# main_board.net
KiCad netlist of a schematic drawn in EAGLE
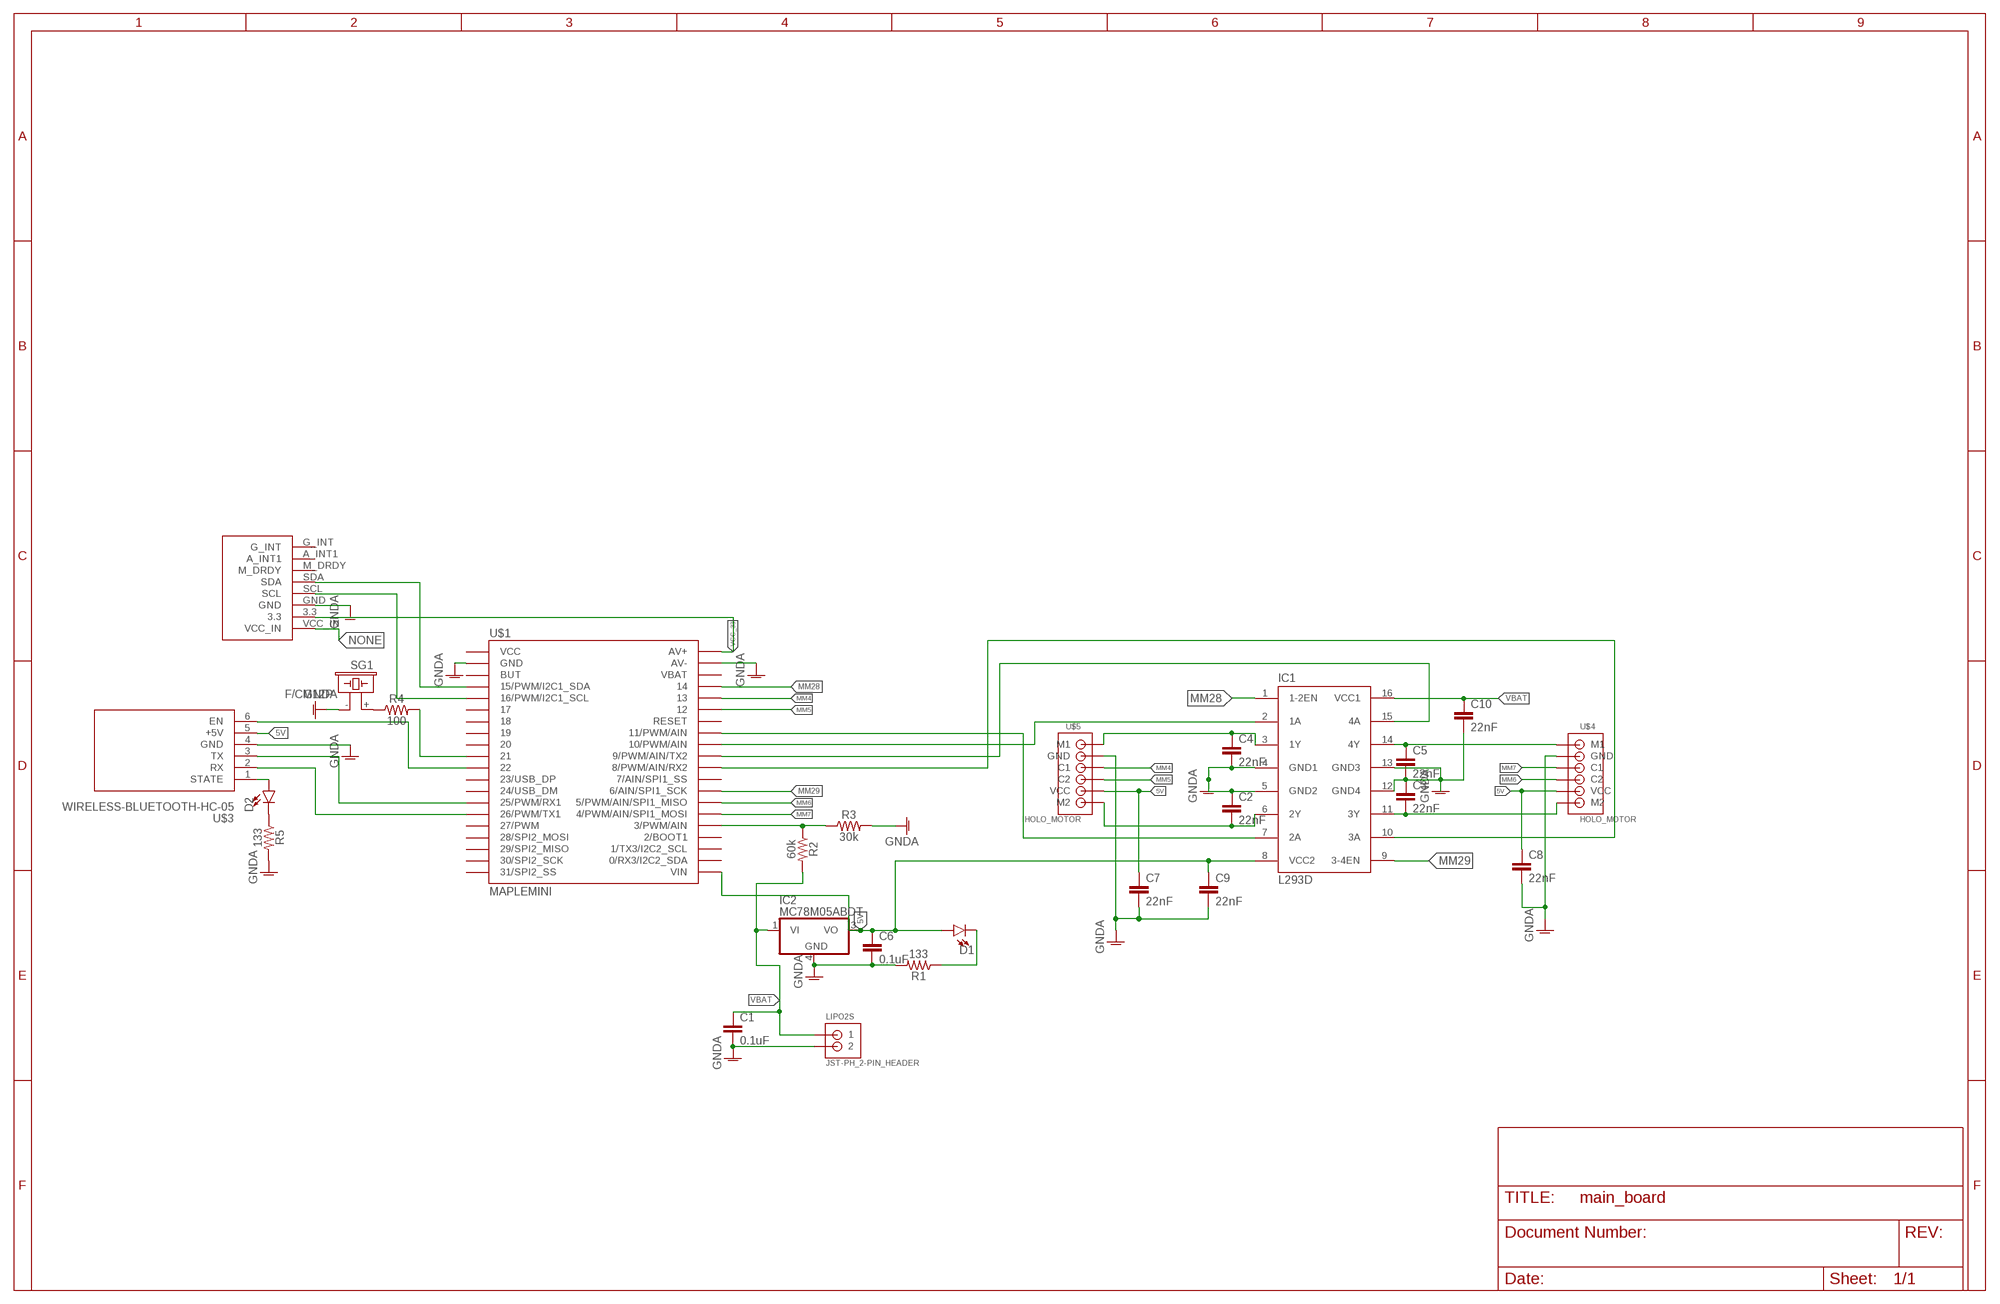
[diagram p0: schematic, sheet 1]

(export (version "E")
  (design (tool "Eeschema 10.0.6"))
  (components
    (comp (ref "C1")
      (value "0.1uF")
      (footprint "eagle-import:0603")
      (libsource (lib "eagle-import") (part "0.1UF-0603-25V-(+80/-20%)"))
    )
    (comp (ref "C2")
      (value "22nF")
      (footprint "eagle-import:0603")
      (libsource (lib "eagle-import") (part "22NF/22,000PF-0603-50V-10%"))
    )
    (comp (ref "C3")
      (value "22nF")
      (footprint "eagle-import:0603")
      (libsource (lib "eagle-import") (part "22NF/22,000PF-0603-50V-10%"))
    )
    (comp (ref "C4")
      (value "22nF")
      (footprint "eagle-import:0603")
      (libsource (lib "eagle-import") (part "22NF/22,000PF-0603-50V-10%"))
    )
    (comp (ref "C5")
      (value "22nF")
      (footprint "eagle-import:0603")
      (libsource (lib "eagle-import") (part "22NF/22,000PF-0603-50V-10%"))
    )
    (comp (ref "C6")
      (value "0.1uF")
      (footprint "eagle-import:0603")
      (libsource (lib "eagle-import") (part "0.1UF-0603-25V-(+80/-20%)"))
    )
    (comp (ref "C7")
      (value "22nF")
      (footprint "eagle-import:0603")
      (fields (field (name "PROD_ID") "CAP-07885"))
      (libsource (lib "eagle-import") (part "22NF/22,000PF-0603-50V-10%"))
    )
    (comp (ref "C8")
      (value "22nF")
      (footprint "eagle-import:0603")
      (fields (field (name "PROD_ID") "CAP-07885"))
      (libsource (lib "eagle-import") (part "22NF/22,000PF-0603-50V-10%"))
    )
    (comp (ref "C9")
      (value "22nF")
      (footprint "eagle-import:0603")
      (fields (field (name "PROD_ID") "CAP-07885"))
      (libsource (lib "eagle-import") (part "22NF/22,000PF-0603-50V-10%"))
    )
    (comp (ref "C10")
      (value "22nF")
      (footprint "eagle-import:0603")
      (fields (field (name "PROD_ID") "CAP-07885"))
      (libsource (lib "eagle-import") (part "22NF/22,000PF-0603-50V-10%"))
    )
    (comp (ref "D1")
      (value "LED-FKIT-1206")
      (footprint "eagle-import:FKIT-LED-1206")
      (libsource (lib "eagle-import") (part "LED-FKIT-1206"))
    )
    (comp (ref "D2")
      (value "LED-FKIT-1206")
      (footprint "eagle-import:FKIT-LED-1206")
      (libsource (lib "eagle-import") (part "LED-FKIT-1206"))
    )
    (comp (ref "IC1")
      (value "L293D")
      (footprint "eagle-import:DIL16")
      (libsource (lib "eagle-import") (part "L293D"))
    )
    (comp (ref "IC2")
      (value "MC78M05ABDT")
      (footprint "eagle-import:DPACK_3")
      (libsource (lib "eagle-import") (part "MC78M05ABDT"))
    )
    (comp (ref "LIPO2S")
      (value "JST-PH_2-PIN_HEADER")
      (footprint "eagle-import:JST_B2B-PH_HEADER")
      (libsource (lib "eagle-import") (part "JST-PH_2-PIN_HEADER"))
    )
    (comp (ref "R1")
      (value "133")
      (footprint "eagle-import:0603")
      (libsource (lib "eagle-import") (part "0.27OHM-0603-1/10W-1%"))
    )
    (comp (ref "R2")
      (value "60k")
      (footprint "eagle-import:0603")
      (libsource (lib "eagle-import") (part "0.27OHM-0603-1/10W-1%"))
    )
    (comp (ref "R3")
      (value "30k")
      (footprint "eagle-import:0603")
      (libsource (lib "eagle-import") (part "0.27OHM-0603-1/10W-1%"))
    )
    (comp (ref "R4")
      (value "100")
      (footprint "eagle-import:0603")
      (libsource (lib "eagle-import") (part "0.27OHM-0603-1/10W-1%"))
    )
    (comp (ref "R5")
      (value "133")
      (footprint "eagle-import:0603")
      (libsource (lib "eagle-import") (part "0.27OHM-0603-1/10W-1%"))
    )
    (comp (ref "SG1")
      (value "F/CM12P")
      (footprint "eagle-import:F_CM12P")
      (libsource (lib "eagle-import") (part "F/CM12P"))
    )
    (comp (ref "U$1")
      (value "MAPLEMINI")
      (footprint "eagle-import:20-DIP")
      (libsource (lib "eagle-import") (part "MAPLEMINI"))
    )
    (comp (ref "U$3")
      (value "WIRELESS-BLUETOOTH-HC-05")
      (footprint "eagle-import:WIRELESS-BLUETOOTH-HC-05")
      (libsource (lib "eagle-import") (part "WIRELESS-BLUETOOTH-HC-05"))
    )
    (comp (ref "U$4")
      (value "HOLO_MOTOR")
      (footprint "eagle-import:HOLO_MOTOR")
      (libsource (lib "eagle-import") (part "HOLO_MOTOR"))
    )
    (comp (ref "U$5")
      (value "HOLO_MOTOR")
      (footprint "eagle-import:HOLO_MOTOR")
      (libsource (lib "eagle-import") (part "HOLO_MOTOR"))
    )
    (comp (ref "U$6")
      (value "GY-85")
      (footprint "eagle-import:GY-85")
      (libsource (lib "eagle-import") (part "GY-85"))
    )
  )
  (nets
    (net (code "1") (name "5V") (class "Default")
      (node (ref "C6") (pin "1") (pinfunction "1_1") (pintype "passive"))
      (node (ref "C7") (pin "1") (pinfunction "1_1") (pintype "passive"))
      (node (ref "C8") (pin "1") (pinfunction "1_1") (pintype "passive"))
      (node (ref "C9") (pin "1") (pinfunction "1_1") (pintype "passive"))
      (node (ref "D1") (pin "A") (pinfunction "A_A") (pintype "passive"))
      (node (ref "IC1") (pin "8") (pinfunction "VCC2_8") (pintype "power_in"))
      (node (ref "IC2") (pin "3") (pinfunction "VO_3") (pintype "passive"))
      (node (ref "U$1") (pin "21") (pinfunction "VIN_21") (pintype "bidirectional"))
      (node (ref "U$3") (pin "5") (pinfunction "+5V_5") (pintype "power_in"))
      (node (ref "U$4") (pin "5") (pinfunction "VCC_5") (pintype "bidirectional"))
      (node (ref "U$5") (pin "5") (pinfunction "VCC_5") (pintype "bidirectional"))
    )
    (net (code "2") (name "GNDA") (class "Default")
      (node (ref "C1") (pin "2") (pinfunction "2_2") (pintype "passive"))
      (node (ref "C10") (pin "2") (pinfunction "2_2") (pintype "passive"))
      (node (ref "C2") (pin "1") (pinfunction "1_1") (pintype "passive"))
      (node (ref "C3") (pin "1") (pinfunction "1_1") (pintype "passive"))
      (node (ref "C4") (pin "2") (pinfunction "2_2") (pintype "passive"))
      (node (ref "C5") (pin "2") (pinfunction "2_2") (pintype "passive"))
      (node (ref "C6") (pin "2") (pinfunction "2_2") (pintype "passive"))
      (node (ref "C7") (pin "2") (pinfunction "2_2") (pintype "passive"))
      (node (ref "C8") (pin "2") (pinfunction "2_2") (pintype "passive"))
      (node (ref "C9") (pin "2") (pinfunction "2_2") (pintype "passive"))
      (node (ref "IC1") (pin "12") (pinfunction "GND4_12") (pintype "power_in"))
      (node (ref "IC1") (pin "13") (pinfunction "GND3_13") (pintype "power_in"))
      (node (ref "IC1") (pin "4") (pinfunction "GND1_4") (pintype "power_in"))
      (node (ref "IC1") (pin "5") (pinfunction "GND2_5") (pintype "power_in"))
      (node (ref "IC2") (pin "4") (pinfunction "GND_4") (pintype "passive"))
      (node (ref "LIPO2S") (pin "P2") (pinfunction "2_P2") (pintype "bidirectional"))
      (node (ref "R1") (pin "2") (pinfunction "2_2") (pintype "passive"))
      (node (ref "R3") (pin "2") (pinfunction "2_2") (pintype "passive"))
      (node (ref "R5") (pin "2") (pinfunction "2_2") (pintype "passive"))
      (node (ref "SG1") (pin "-") (pinfunction "2_-") (pintype "passive"))
      (node (ref "U$1") (pin "2") (pinfunction "GND_2") (pintype "bidirectional"))
      (node (ref "U$1") (pin "39") (pinfunction "AV-_39") (pintype "bidirectional"))
      (node (ref "U$3") (pin "4") (pinfunction "GND_4") (pintype "power_in"))
      (node (ref "U$4") (pin "2") (pinfunction "GND_2") (pintype "bidirectional"))
      (node (ref "U$5") (pin "2") (pinfunction "GND_2") (pintype "bidirectional"))
      (node (ref "U$6") (pin "GND") (pinfunction "GND_GND") (pintype "bidirectional"))
    )
    (net (code "3") (name "MM4") (class "Default")
      (node (ref "U$1") (pin "36") (pinfunction "13_36") (pintype "bidirectional"))
      (node (ref "U$5") (pin "3") (pinfunction "C1_3") (pintype "bidirectional"))
    )
    (net (code "4") (name "MM5") (class "Default")
      (node (ref "U$1") (pin "35") (pinfunction "12_35") (pintype "bidirectional"))
      (node (ref "U$5") (pin "4") (pinfunction "C2_4") (pintype "bidirectional"))
    )
    (net (code "5") (name "MM6") (class "Default")
      (node (ref "U$1") (pin "27") (pinfunction "5/PWM/AIN/SPI1_MISO_27") (pintype "bidirectional"))
      (node (ref "U$4") (pin "4") (pinfunction "C2_4") (pintype "bidirectional"))
    )
    (net (code "6") (name "MM7") (class "Default")
      (node (ref "U$1") (pin "26") (pinfunction "4/PWM/AIN/SPI1_MOSI_26") (pintype "bidirectional"))
      (node (ref "U$4") (pin "3") (pinfunction "C1_3") (pintype "bidirectional"))
    )
    (net (code "7") (name "MM28") (class "Default")
      (node (ref "IC1") (pin "1") (pinfunction "1-2EN_1") (pintype "input"))
      (node (ref "U$1") (pin "37") (pinfunction "14_37") (pintype "bidirectional"))
    )
    (net (code "8") (name "MM29") (class "Default")
      (node (ref "IC1") (pin "9") (pinfunction "3-4EN_9") (pintype "input"))
      (node (ref "U$1") (pin "28") (pinfunction "6/AIN/SPI1_SCK_28") (pintype "bidirectional"))
    )
    (net (code "9") (name "NONE") (class "Default")
      (node (ref "U$6") (pin "VCC_IN") (pinfunction "VCC_IN_VCC_IN") (pintype "bidirectional"))
    )
    (net (code "10") (name "Net-(D1-PadC)") (class "Default")
      (node (ref "D1") (pin "C") (pinfunction "C_C") (pintype "passive"))
      (node (ref "R1") (pin "1") (pinfunction "1_1") (pintype "passive"))
    )
    (net (code "11") (name "Net-(D2-PadC)") (class "Default")
      (node (ref "D2") (pin "C") (pinfunction "C_C") (pintype "passive"))
      (node (ref "R5") (pin "1") (pinfunction "1_1") (pintype "passive"))
    )
    (net (code "12") (name "Net-(IC1-1A)") (class "Default")
      (node (ref "IC1") (pin "2") (pinfunction "1A_2") (pintype "input"))
      (node (ref "U$1") (pin "32") (pinfunction "10/PWM/AIN_32") (pintype "bidirectional"))
    )
    (net (code "13") (name "Net-(IC1-1Y)") (class "Default")
      (node (ref "C4") (pin "1") (pinfunction "1_1") (pintype "passive"))
      (node (ref "IC1") (pin "3") (pinfunction "1Y_3") (pintype "output"))
      (node (ref "U$5") (pin "1") (pinfunction "M1_1") (pintype "bidirectional"))
    )
    (net (code "14") (name "Net-(IC1-2A)") (class "Default")
      (node (ref "IC1") (pin "7") (pinfunction "2A_7") (pintype "input"))
      (node (ref "U$1") (pin "33") (pinfunction "11/PWM/AIN_33") (pintype "bidirectional"))
    )
    (net (code "15") (name "Net-(IC1-2Y)") (class "Default")
      (node (ref "C2") (pin "2") (pinfunction "2_2") (pintype "passive"))
      (node (ref "IC1") (pin "6") (pinfunction "2Y_6") (pintype "output"))
      (node (ref "U$5") (pin "6") (pinfunction "M2_6") (pintype "bidirectional"))
    )
    (net (code "16") (name "Net-(IC1-3A)") (class "Default")
      (node (ref "IC1") (pin "10") (pinfunction "3A_10") (pintype "input"))
      (node (ref "U$1") (pin "30") (pinfunction "8/PWM/AIN/RX2_30") (pintype "bidirectional"))
    )
    (net (code "17") (name "Net-(IC1-3Y)") (class "Default")
      (node (ref "C3") (pin "2") (pinfunction "2_2") (pintype "passive"))
      (node (ref "IC1") (pin "11") (pinfunction "3Y_11") (pintype "output"))
      (node (ref "U$4") (pin "6") (pinfunction "M2_6") (pintype "bidirectional"))
    )
    (net (code "18") (name "Net-(IC1-4A)") (class "Default")
      (node (ref "IC1") (pin "15") (pinfunction "4A_15") (pintype "input"))
      (node (ref "U$1") (pin "31") (pinfunction "9/PWM/AIN/TX2_31") (pintype "bidirectional"))
    )
    (net (code "19") (name "Net-(IC1-4Y)") (class "Default")
      (node (ref "C5") (pin "1") (pinfunction "1_1") (pintype "passive"))
      (node (ref "IC1") (pin "14") (pinfunction "4Y_14") (pintype "output"))
      (node (ref "U$4") (pin "1") (pinfunction "M1_1") (pintype "bidirectional"))
    )
    (net (code "20") (name "Net-(SG1-1)") (class "Default")
      (node (ref "R4") (pin "1") (pinfunction "1_1") (pintype "passive"))
      (node (ref "SG1") (pin "+") (pinfunction "1_+") (pintype "passive"))
    )
    (net (code "21") (name "Net-(U$1-3{slash}PWM{slash}AIN)") (class "Default")
      (node (ref "R2") (pin "1") (pinfunction "1_1") (pintype "passive"))
      (node (ref "R3") (pin "1") (pinfunction "1_1") (pintype "passive"))
      (node (ref "U$1") (pin "25") (pinfunction "3/PWM/AIN_25") (pintype "bidirectional"))
    )
    (net (code "22") (name "Net-(U$1-15{slash}PWM{slash}I2C1_SDA)") (class "Default")
      (node (ref "U$1") (pin "4") (pinfunction "15/PWM/I2C1_SDA_4") (pintype "bidirectional"))
      (node (ref "U$6") (pin "SDA") (pinfunction "SDA_SDA") (pintype "bidirectional"))
    )
    (net (code "23") (name "Net-(U$1-16{slash}PWM{slash}I2C1_SCL)") (class "Default")
      (node (ref "U$1") (pin "5") (pinfunction "16/PWM/I2C1_SCL_5") (pintype "bidirectional"))
      (node (ref "U$6") (pin "SCL") (pinfunction "SCL_SCL") (pintype "bidirectional"))
    )
    (net (code "24") (name "Net-(U$1-21)") (class "Default")
      (node (ref "R4") (pin "2") (pinfunction "2_2") (pintype "passive"))
      (node (ref "U$1") (pin "10") (pinfunction "21_10") (pintype "bidirectional"))
    )
    (net (code "25") (name "Net-(U$1-22)") (class "Default")
      (node (ref "U$1") (pin "11") (pinfunction "22_11") (pintype "bidirectional"))
      (node (ref "U$3") (pin "6") (pinfunction "EN_6") (pintype "bidirectional"))
    )
    (net (code "26") (name "Net-(U$1-25{slash}PWM{slash}RX1)") (class "Default")
      (node (ref "U$1") (pin "14") (pinfunction "25/PWM/RX1_14") (pintype "bidirectional"))
      (node (ref "U$3") (pin "3") (pinfunction "TX_3") (pintype "bidirectional"))
    )
    (net (code "27") (name "Net-(U$1-26{slash}PWM{slash}TX1)") (class "Default")
      (node (ref "U$1") (pin "15") (pinfunction "26/PWM/TX1_15") (pintype "bidirectional"))
      (node (ref "U$3") (pin "2") (pinfunction "RX_2") (pintype "bidirectional"))
    )
    (net (code "28") (name "Net-(U$3-STATE)") (class "Default")
      (node (ref "D2") (pin "A") (pinfunction "A_A") (pintype "passive"))
      (node (ref "U$3") (pin "1") (pinfunction "STATE_1") (pintype "bidirectional"))
    )
    (net (code "29") (name "VBAT") (class "Default")
      (node (ref "C1") (pin "1") (pinfunction "1_1") (pintype "passive"))
      (node (ref "C10") (pin "1") (pinfunction "1_1") (pintype "passive"))
      (node (ref "IC1") (pin "16") (pinfunction "VCC1_16") (pintype "power_in"))
      (node (ref "IC2") (pin "1") (pinfunction "VI_1") (pintype "input"))
      (node (ref "LIPO2S") (pin "P1") (pinfunction "1_P1") (pintype "bidirectional"))
      (node (ref "R2") (pin "2") (pinfunction "2_2") (pintype "passive"))
    )
    (net (code "30") (name "VCC_33") (class "Default")
      (node (ref "U$1") (pin "40") (pinfunction "AV+_40") (pintype "bidirectional"))
      (node (ref "U$6") (pin "3.3") (pinfunction "3.3_3.3") (pintype "bidirectional"))
    )
    (net (code "31") (name "unconnected-(U$1-0{slash}RX3{slash}I2C2_SDA-Pad22)") (class "Default")
      (node (ref "U$1") (pin "22") (pinfunction "0/RX3/I2C2_SDA_22") (pintype "bidirectional"))
    )
    (net (code "32") (name "unconnected-(U$1-1{slash}TX3{slash}I2C2_SCL-Pad23)") (class "Default")
      (node (ref "U$1") (pin "23") (pinfunction "1/TX3/I2C2_SCL_23") (pintype "bidirectional"))
    )
    (net (code "33") (name "unconnected-(U$1-2{slash}BOOT1-Pad24)") (class "Default")
      (node (ref "U$1") (pin "24") (pinfunction "2/BOOT1_24") (pintype "bidirectional"))
    )
    (net (code "34") (name "unconnected-(U$1-7{slash}AIN{slash}SPI1_SS-Pad29)") (class "Default")
      (node (ref "U$1") (pin "29") (pinfunction "7/AIN/SPI1_SS_29") (pintype "bidirectional"))
    )
    (net (code "35") (name "unconnected-(U$1-17-Pad6)") (class "Default")
      (node (ref "U$1") (pin "6") (pinfunction "17_6") (pintype "bidirectional"))
    )
    (net (code "36") (name "unconnected-(U$1-18-Pad7)") (class "Default")
      (node (ref "U$1") (pin "7") (pinfunction "18_7") (pintype "bidirectional"))
    )
    (net (code "37") (name "unconnected-(U$1-19-Pad8)") (class "Default")
      (node (ref "U$1") (pin "8") (pinfunction "19_8") (pintype "bidirectional"))
    )
    (net (code "38") (name "unconnected-(U$1-20-Pad9)") (class "Default")
      (node (ref "U$1") (pin "9") (pinfunction "20_9") (pintype "bidirectional"))
    )
    (net (code "39") (name "unconnected-(U$1-23{slash}USB_DP-Pad12)") (class "Default")
      (node (ref "U$1") (pin "12") (pinfunction "23/USB_DP_12") (pintype "bidirectional"))
    )
    (net (code "40") (name "unconnected-(U$1-24{slash}USB_DM-Pad13)") (class "Default")
      (node (ref "U$1") (pin "13") (pinfunction "24/USB_DM_13") (pintype "bidirectional"))
    )
    (net (code "41") (name "unconnected-(U$1-27{slash}PWM-Pad16)") (class "Default")
      (node (ref "U$1") (pin "16") (pinfunction "27/PWM_16") (pintype "bidirectional"))
    )
    (net (code "42") (name "unconnected-(U$1-28{slash}SPI2_MOSI-Pad17)") (class "Default")
      (node (ref "U$1") (pin "17") (pinfunction "28/SPI2_MOSI_17") (pintype "bidirectional"))
    )
    (net (code "43") (name "unconnected-(U$1-29{slash}SPI2_MISO-Pad18)") (class "Default")
      (node (ref "U$1") (pin "18") (pinfunction "29/SPI2_MISO_18") (pintype "bidirectional"))
    )
    (net (code "44") (name "unconnected-(U$1-30{slash}SPI2_SCK-Pad19)") (class "Default")
      (node (ref "U$1") (pin "19") (pinfunction "30/SPI2_SCK_19") (pintype "bidirectional"))
    )
    (net (code "45") (name "unconnected-(U$1-31{slash}SPI2_SS-Pad20)") (class "Default")
      (node (ref "U$1") (pin "20") (pinfunction "31/SPI2_SS_20") (pintype "bidirectional"))
    )
    (net (code "46") (name "unconnected-(U$1-BUT-Pad3)") (class "Default")
      (node (ref "U$1") (pin "3") (pinfunction "BUT_3") (pintype "bidirectional"))
    )
    (net (code "47") (name "unconnected-(U$1-RESET-Pad34)") (class "Default")
      (node (ref "U$1") (pin "34") (pinfunction "RESET_34") (pintype "bidirectional"))
    )
    (net (code "48") (name "unconnected-(U$1-VBAT-Pad38)") (class "Default")
      (node (ref "U$1") (pin "38") (pinfunction "VBAT_38") (pintype "bidirectional"))
    )
    (net (code "49") (name "unconnected-(U$1-VCC-Pad1)") (class "Default")
      (node (ref "U$1") (pin "1") (pinfunction "VCC_1") (pintype "bidirectional"))
    )
    (net (code "50") (name "unconnected-(U$6-PadA_INT1)") (class "Default")
      (node (ref "U$6") (pin "A_INT1") (pinfunction "A_INT1_A_INT1") (pintype "bidirectional"))
    )
    (net (code "51") (name "unconnected-(U$6-PadG_INT)") (class "Default")
      (node (ref "U$6") (pin "G_INT") (pinfunction "G_INT_G_INT") (pintype "bidirectional"))
    )
    (net (code "52") (name "unconnected-(U$6-PadM_DRDY)") (class "Default")
      (node (ref "U$6") (pin "M_DRDY") (pinfunction "M_DRDY_M_DRDY") (pintype "bidirectional"))
    )
  )
)
